# MCU.net
KiCad netlist of a schematic drawn in Altium Designer
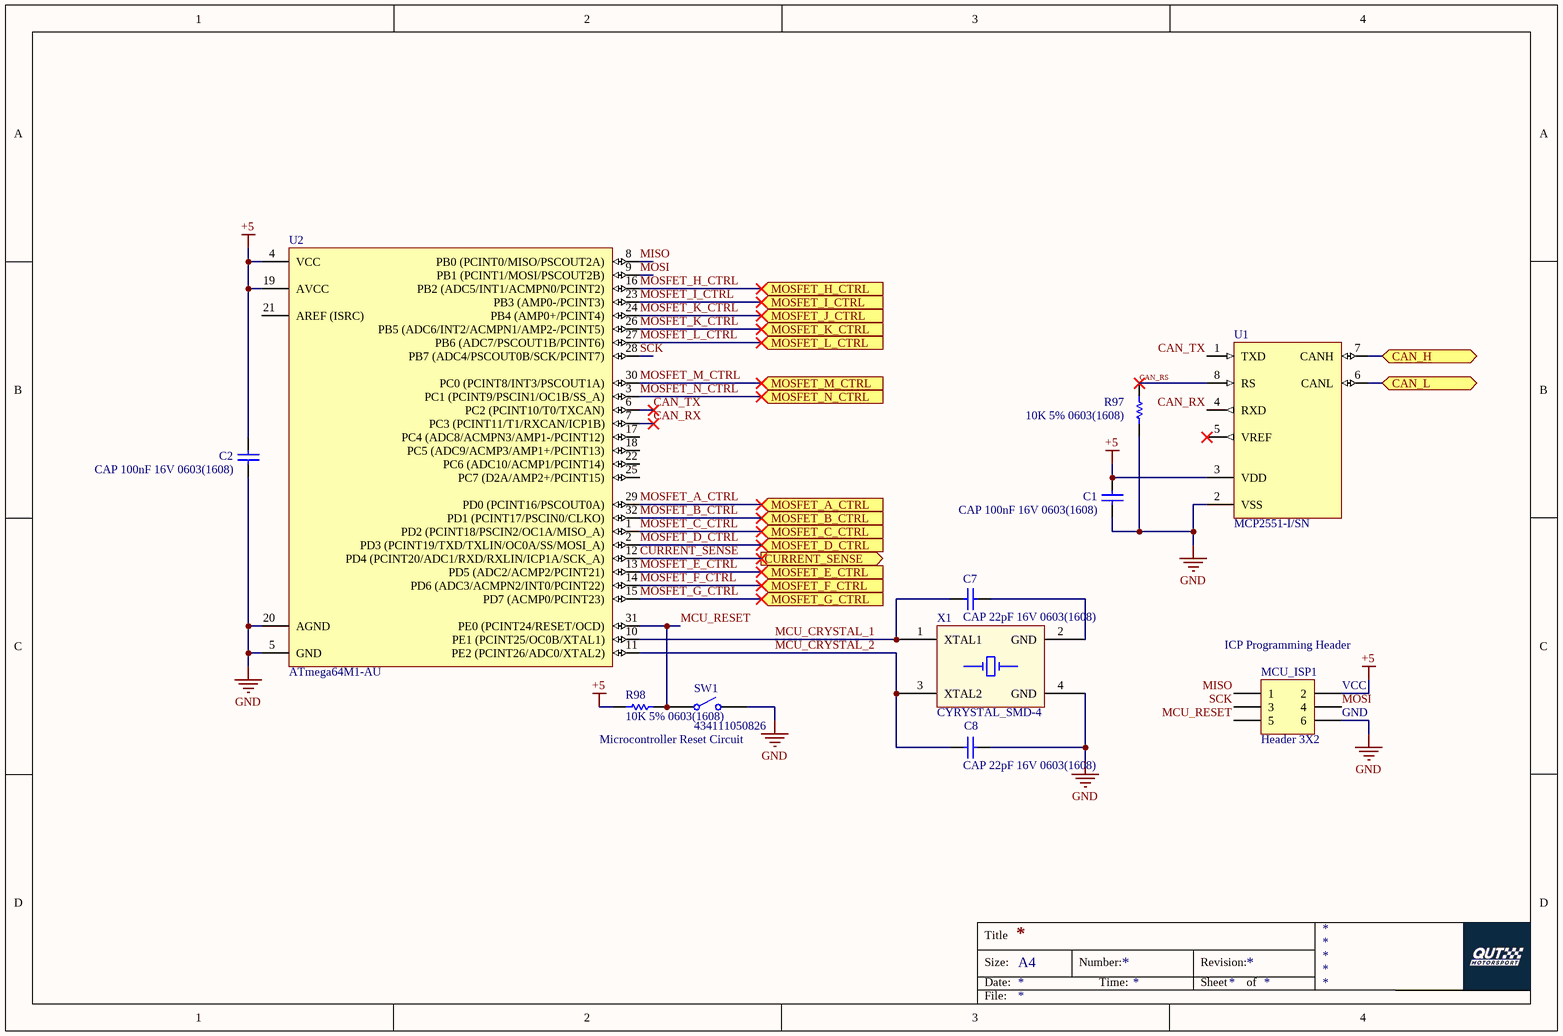
[diagram p0: MCU.SchDoc]

(export (version "E")
  (design (tool "Eeschema 10.0.6"))
  (components
    (comp (ref "C1")
      (value "CAP 100nF 16V 0603(1608)")
      (footprint "CAPC0603(1608)100_M")
      (description "CAP 100nF 16V ±5% 0603 (1608 Metric) Thickness 1mm SMD")
      (fields (field (name "TOLERANCE") "Â±5%"))
      (libsource (lib "Altium Content Vault") (part "CAP"))
    )
    (comp (ref "C2")
      (value "CAP 100nF 16V 0603(1608)")
      (footprint "CAPC0603(1608)100_M")
      (description "CAP 100nF 16V ±5% 0603 (1608 Metric) Thickness 1mm SMD")
      (fields (field (name "TOLERANCE") "Â±5%"))
      (libsource (lib "Altium Content Vault") (part "CAP"))
    )
    (comp (ref "C7")
      (value "CAP 22pF 16V 0603(1608)")
      (footprint "CAPC0603(1608)100_N")
      (description "CAP 22pF 16V ±5% 0603 (1608 Metric) Thickness 1mm SMD")
      (fields (field (name "TOLERANCE") "Â±5%"))
      (libsource (lib "Altium Content Vault") (part "CAP"))
    )
    (comp (ref "C8")
      (value "CAP 22pF 16V 0603(1608)")
      (footprint "CAPC0603(1608)100_N")
      (description "CAP 22pF 16V ±5% 0603 (1608 Metric) Thickness 1mm SMD")
      (fields (field (name "TOLERANCE") "Â±5%"))
      (libsource (lib "Altium Content Vault") (part "CAP"))
    )
    (comp (ref "MCU_ISP1")
      (value "Header 3X2")
      (footprint "HDR2X3")
      (description "Header, 3-Pin, Dual row")
      (fields (field (name "PUBLISHER") "Altium Limited"))
      (libsource (lib "Miscellaneous Connectors") (part "Header 3X2"))
    )
    (comp (ref "R97")
      (value "10K 5% 0603(1608)")
      (footprint "RESC0603(1608)_N")
      (description "10K 0.1W 5% 0603 (1608 Metric)  SMD")
      (fields (field (name "TOLERANCE") "5 %") (field (name "POWER") "0.1 W"))
      (libsource (lib "Altium Content Vault") (part "RES"))
    )
    (comp (ref "R98")
      (value "10K 5% 0603(1608)")
      (footprint "RESC0603(1608)_N")
      (description "10K 0.1W 5% 0603 (1608 Metric)  SMD")
      (fields (field (name "TOLERANCE") "5 %") (field (name "POWER") "0.1 W"))
      (libsource (lib "Altium Content Vault") (part "RES"))
    )
    (comp (ref "SW1")
      (value "434111050826")
      (footprint "434111050826")
      (description "WS-TASV SMD Tact Switch 6.0X3.5 mm")
      (fields (field (name "MANUFACTURER") "Wuerth Elektronik"))
      (libsource (lib "Altium Content Vault") (part "WE-TACT-SW-2"))
    )
    (comp (ref "U1")
      (value "MCP2551-I/SN")
      (footprint "SOIC-SN8_N")
      (description "High-Speed CAN Transceiver, 8-Pin SOIC, Industrial Temperature")
      (libsource (lib "Altium Content Vault") (part "COM-TRX-MCP2551-8"))
    )
    (comp (ref "U2")
      (value "ATmega64M1-AU")
      (footprint "32A_L")
      (libsource (lib "Altium Content Vault") (part "MC-8B-ATM16M1-SQ32"))
    )
    (comp (ref "X1")
      (value "CYRYSTAL_SMD-4")
      (footprint "SMD-4_CRYSTAL_5x3.2mm")
      (libsource (lib "RPI GPIO BOARD") (part "CYRYSTAL_SMD-4"))
    )
  )
  (nets
    (net (code "1") (name "+5") (class "Default")
      (node (ref "C1") (pin "2") (pinfunction "2_2") (pintype "passive"))
      (node (ref "C2") (pin "2") (pinfunction "2_2") (pintype "passive"))
      (node (ref "MCU_ISP1") (pin "2") (pinfunction "2_2") (pintype "passive"))
      (node (ref "R98") (pin "2") (pinfunction "2_2") (pintype "passive"))
      (node (ref "U1") (pin "3") (pinfunction "VDD_3") (pintype "power_in"))
      (node (ref "U2") (pin "19") (pinfunction "AVCC_19") (pintype "power_in"))
      (node (ref "U2") (pin "4") (pinfunction "VCC_4") (pintype "power_in"))
    )
    (net (code "2") (name "/CAN_H") (class "Default")
      (node (ref "U1") (pin "7") (pinfunction "CANH_7") (pintype "bidirectional"))
    )
    (net (code "3") (name "/CAN_L") (class "Default")
      (node (ref "U1") (pin "6") (pinfunction "CANL_6") (pintype "bidirectional"))
    )
    (net (code "4") (name "/CAN_RS") (class "Default")
      (node (ref "R97") (pin "2") (pinfunction "2_2") (pintype "passive"))
      (node (ref "U1") (pin "8") (pinfunction "RS_8") (pintype "input"))
    )
    (net (code "5") (name "/CAN_RX") (class "Default")
      (node (ref "U1") (pin "4") (pinfunction "RXD_4") (pintype "output"))
      (node (ref "U2") (pin "7") (pinfunction "PC3_(PCINT11/T1/RXCAN/ICP1B)_7") (pintype "bidirectional"))
    )
    (net (code "6") (name "/CAN_TX") (class "Default")
      (node (ref "U1") (pin "1") (pinfunction "TXD_1") (pintype "input"))
      (node (ref "U2") (pin "6") (pinfunction "PC2_(PCINT10/T0/TXCAN)_6") (pintype "bidirectional"))
    )
    (net (code "7") (name "/CURRENT_SENSE") (class "Default")
      (node (ref "U2") (pin "12") (pinfunction "PD4_(PCINT20/ADC1/RXD/RXLIN/ICP1A/SCK_A)_12") (pintype "bidirectional+no_connect"))
    )
    (net (code "8") (name "/MCU_CRYSTAL_1") (class "Default")
      (node (ref "C7") (pin "1") (pinfunction "1_1") (pintype "passive"))
      (node (ref "U2") (pin "10") (pinfunction "PE1_(PCINT25/OC0B/XTAL1)_10") (pintype "bidirectional"))
      (node (ref "X1") (pin "1") (pinfunction "XTAL1_1") (pintype "passive"))
    )
    (net (code "9") (name "/MCU_CRYSTAL_2") (class "Default")
      (node (ref "C8") (pin "1") (pinfunction "1_1") (pintype "passive"))
      (node (ref "U2") (pin "11") (pinfunction "PE2_(PCINT26/ADC0/XTAL2)_11") (pintype "bidirectional"))
      (node (ref "X1") (pin "3") (pinfunction "XTAL2_3") (pintype "passive"))
    )
    (net (code "10") (name "/MCU_RESET") (class "Default")
      (node (ref "MCU_ISP1") (pin "5") (pinfunction "5_5") (pintype "passive"))
      (node (ref "R98") (pin "1") (pinfunction "1_1") (pintype "passive"))
      (node (ref "SW1") (pin "1") (pinfunction "1_1") (pintype "passive"))
      (node (ref "U2") (pin "31") (pinfunction "PE0_(PCINT24/RESET/OCD)_31") (pintype "bidirectional"))
    )
    (net (code "11") (name "/MISO") (class "Default")
      (node (ref "MCU_ISP1") (pin "1") (pinfunction "1_1") (pintype "passive"))
      (node (ref "U2") (pin "8") (pinfunction "PB0_(PCINT0/MISO/PSCOUT2A)_8") (pintype "bidirectional"))
    )
    (net (code "12") (name "/MOSFET_A_CTRL") (class "Default")
      (node (ref "U2") (pin "29") (pinfunction "PD0_(PCINT16/PSCOUT0A)_29") (pintype "bidirectional+no_connect"))
    )
    (net (code "13") (name "/MOSFET_B_CTRL") (class "Default")
      (node (ref "U2") (pin "32") (pinfunction "PD1_(PCINT17/PSCIN0/CLKO)_32") (pintype "bidirectional+no_connect"))
    )
    (net (code "14") (name "/MOSFET_C_CTRL") (class "Default")
      (node (ref "U2") (pin "1") (pinfunction "PD2_(PCINT18/PSCIN2/OC1A/MISO_A)_1") (pintype "bidirectional+no_connect"))
    )
    (net (code "15") (name "/MOSFET_D_CTRL") (class "Default")
      (node (ref "U2") (pin "2") (pinfunction "PD3_(PCINT19/TXD/TXLIN/OC0A/SS/MOSI_A)_2") (pintype "bidirectional+no_connect"))
    )
    (net (code "16") (name "/MOSFET_E_CTRL") (class "Default")
      (node (ref "U2") (pin "13") (pinfunction "PD5_(ADC2/ACMP2/PCINT21)_13") (pintype "bidirectional+no_connect"))
    )
    (net (code "17") (name "/MOSFET_F_CTRL") (class "Default")
      (node (ref "U2") (pin "14") (pinfunction "PD6_(ADC3/ACMPN2/INT0/PCINT22)_14") (pintype "bidirectional+no_connect"))
    )
    (net (code "18") (name "/MOSFET_G_CTRL") (class "Default")
      (node (ref "U2") (pin "15") (pinfunction "PD7_(ACMP0/PCINT23)_15") (pintype "bidirectional+no_connect"))
    )
    (net (code "19") (name "/MOSFET_H_CTRL") (class "Default")
      (node (ref "U2") (pin "16") (pinfunction "PB2_(ADC5/INT1/ACMPN0/PCINT2)_16") (pintype "bidirectional+no_connect"))
    )
    (net (code "20") (name "/MOSFET_I_CTRL") (class "Default")
      (node (ref "U2") (pin "23") (pinfunction "PB3_(AMP0-/PCINT3)_23") (pintype "bidirectional+no_connect"))
    )
    (net (code "21") (name "/MOSFET_K_CTRL") (class "Default")
      (node (ref "U2") (pin "24") (pinfunction "PB4_(AMP0+/PCINT4)_24") (pintype "bidirectional"))
      (node (ref "U2") (pin "26") (pinfunction "PB5_(ADC6/INT2/ACMPN1/AMP2-/PCINT5)_26") (pintype "bidirectional"))
    )
    (net (code "22") (name "/MOSFET_L_CTRL") (class "Default")
      (node (ref "U2") (pin "27") (pinfunction "PB6_(ADC7/PSCOUT1B/PCINT6)_27") (pintype "bidirectional+no_connect"))
    )
    (net (code "23") (name "/MOSFET_M_CTRL") (class "Default")
      (node (ref "U2") (pin "30") (pinfunction "PC0_(PCINT8/INT3/PSCOUT1A)_30") (pintype "bidirectional+no_connect"))
    )
    (net (code "24") (name "/MOSFET_N_CTRL") (class "Default")
      (node (ref "U2") (pin "3") (pinfunction "PC1_(PCINT9/PSCIN1/OC1B/SS_A)_3") (pintype "bidirectional+no_connect"))
    )
    (net (code "25") (name "/MOSI") (class "Default")
      (node (ref "MCU_ISP1") (pin "4") (pinfunction "4_4") (pintype "passive"))
      (node (ref "U2") (pin "9") (pinfunction "PB1_(PCINT1/MOSI/PSCOUT2B)_9") (pintype "bidirectional"))
    )
    (net (code "26") (name "/SCK") (class "Default")
      (node (ref "MCU_ISP1") (pin "3") (pinfunction "3_3") (pintype "passive"))
      (node (ref "U2") (pin "28") (pinfunction "PB7_(ADC4/PSCOUT0B/SCK/PCINT7)_28") (pintype "bidirectional"))
    )
    (net (code "27") (name "GND") (class "Default")
      (node (ref "C1") (pin "1") (pinfunction "1_1") (pintype "passive"))
      (node (ref "C2") (pin "1") (pinfunction "1_1") (pintype "passive"))
      (node (ref "C8") (pin "2") (pinfunction "2_2") (pintype "passive"))
      (node (ref "MCU_ISP1") (pin "6") (pinfunction "6_6") (pintype "passive"))
      (node (ref "R97") (pin "1") (pinfunction "1_1") (pintype "passive"))
      (node (ref "SW1") (pin "2") (pinfunction "2_2") (pintype "passive"))
      (node (ref "U1") (pin "2") (pinfunction "VSS_2") (pintype "power_in"))
      (node (ref "U2") (pin "20") (pinfunction "AGND_20") (pintype "power_in"))
      (node (ref "U2") (pin "5") (pinfunction "GND_5") (pintype "power_in"))
      (node (ref "X1") (pin "4") (pinfunction "GND_4") (pintype "passive"))
    )
    (net (code "28") (name "Net-(C7-Pad2)") (class "Default")
      (node (ref "C7") (pin "2") (pinfunction "2_2") (pintype "passive"))
      (node (ref "X1") (pin "2") (pinfunction "GND_2") (pintype "passive"))
    )
    (net (code "29") (name "unconnected-(U1-VREF-Pad5)") (class "Default")
      (node (ref "U1") (pin "5") (pinfunction "VREF_5") (pintype "output+no_connect"))
    )
    (net (code "30") (name "unconnected-(U2-AREF_(ISRC)-Pad21)") (class "Default")
      (node (ref "U2") (pin "21") (pinfunction "AREF_(ISRC)_21") (pintype "power_in"))
    )
    (net (code "31") (name "unconnected-(U2-PC4_(ADC8{slash}ACMPN3{slash}AMP1-{slash}PCINT12)-Pad17)") (class "Default")
      (node (ref "U2") (pin "17") (pinfunction "PC4_(ADC8/ACMPN3/AMP1-/PCINT12)_17") (pintype "bidirectional"))
    )
    (net (code "32") (name "unconnected-(U2-PC5_(ADC9{slash}ACMP3{slash}AMP1+{slash}PCINT13)-Pad18)") (class "Default")
      (node (ref "U2") (pin "18") (pinfunction "PC5_(ADC9/ACMP3/AMP1+/PCINT13)_18") (pintype "bidirectional"))
    )
    (net (code "33") (name "unconnected-(U2-PC6_(ADC10{slash}ACMP1{slash}PCINT14)-Pad22)") (class "Default")
      (node (ref "U2") (pin "22") (pinfunction "PC6_(ADC10/ACMP1/PCINT14)_22") (pintype "bidirectional"))
    )
    (net (code "34") (name "unconnected-(U2-PC7_(D2A{slash}AMP2+{slash}PCINT15)-Pad25)") (class "Default")
      (node (ref "U2") (pin "25") (pinfunction "PC7_(D2A/AMP2+/PCINT15)_25") (pintype "bidirectional"))
    )
  )
)
